# Tube.net
KiCad netlist of a schematic drawn in Altium Designer
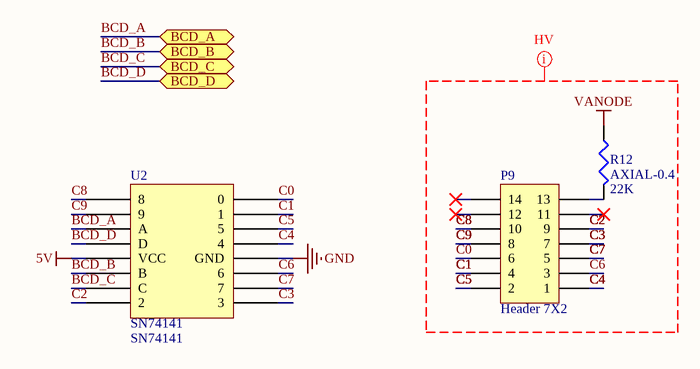
[diagram p0: Tube.SchDoc]

(export (version "E")
  (design (tool "Eeschema 10.0.6"))
  (components
    (comp (ref "P9")
      (value "Header 7X2")
      (footprint "HDR2X7")
      (description "Header, 7-Pin, Dual row")
      (fields (field (name "PUBLISHER") "Altium Limited"))
      (libsource (lib "Miscellaneous Connectors") (part "Header 7X2"))
    )
    (comp (ref "R12")
      (value "AXIAL-0.4")
      (footprint "AXIAL-0.4")
      (description "Resistor")
      (fields (field (name "ALTIUM_VALUE") "22K") (field (name "PUBLISHER") "Altium Limited"))
      (libsource (lib "Miscellaneous Devices") (part "Res3"))
    )
    (comp (ref "U2")
      (value "SN74141")
      (footprint "DIP-16")
      (description "BCD-to-Decimal Driver")
      (fields (field (name "PARTNUMBER") "SN74141"))
      (libsource (lib "Schematic_Components") (part "BCD-to-Decimal Driver"))
    )
  )
  (nets
    (net (code "1") (name "/BCD_A") (class "Default")
      (node (ref "U2") (pin "3") (pinfunction "A_3") (pintype "passive"))
    )
    (net (code "2") (name "/BCD_B") (class "Default")
      (node (ref "U2") (pin "6") (pinfunction "B_6") (pintype "passive"))
    )
    (net (code "3") (name "/BCD_C") (class "Default")
      (node (ref "U2") (pin "7") (pinfunction "C_7") (pintype "passive"))
    )
    (net (code "4") (name "/BCD_D") (class "Default")
      (node (ref "U2") (pin "4") (pinfunction "D_4") (pintype "passive"))
    )
    (net (code "5") (name "/C0") (class "Default")
      (node (ref "P9") (pin "6") (pinfunction "6_6") (pintype "passive"))
      (node (ref "U2") (pin "16") (pinfunction "0_16") (pintype "passive"))
    )
    (net (code "6") (name "/C1") (class "Default")
      (node (ref "P9") (pin "4") (pinfunction "4_4") (pintype "passive"))
      (node (ref "U2") (pin "15") (pinfunction "1_15") (pintype "passive"))
    )
    (net (code "7") (name "/C2") (class "Default")
      (node (ref "P9") (pin "9") (pinfunction "9_9") (pintype "passive"))
      (node (ref "U2") (pin "8") (pinfunction "2_8") (pintype "passive"))
    )
    (net (code "8") (name "/C3") (class "Default")
      (node (ref "P9") (pin "7") (pinfunction "7_7") (pintype "passive"))
      (node (ref "U2") (pin "9") (pinfunction "3_9") (pintype "passive"))
    )
    (net (code "9") (name "/C4") (class "Default")
      (node (ref "P9") (pin "1") (pinfunction "1_1") (pintype "passive"))
      (node (ref "U2") (pin "13") (pinfunction "4_13") (pintype "passive"))
    )
    (net (code "10") (name "/C5") (class "Default")
      (node (ref "P9") (pin "2") (pinfunction "2_2") (pintype "passive"))
      (node (ref "U2") (pin "14") (pinfunction "5_14") (pintype "passive"))
    )
    (net (code "11") (name "/C6") (class "Default")
      (node (ref "P9") (pin "3") (pinfunction "3_3") (pintype "passive"))
      (node (ref "U2") (pin "11") (pinfunction "6_11") (pintype "passive"))
    )
    (net (code "12") (name "/C7") (class "Default")
      (node (ref "P9") (pin "5") (pinfunction "5_5") (pintype "passive"))
      (node (ref "U2") (pin "10") (pinfunction "7_10") (pintype "passive"))
    )
    (net (code "13") (name "/C8") (class "Default")
      (node (ref "P9") (pin "10") (pinfunction "10_10") (pintype "passive"))
      (node (ref "U2") (pin "1") (pinfunction "8_1") (pintype "passive"))
    )
    (net (code "14") (name "/C9") (class "Default")
      (node (ref "P9") (pin "8") (pinfunction "8_8") (pintype "passive"))
      (node (ref "U2") (pin "2") (pinfunction "9_2") (pintype "passive"))
    )
    (net (code "15") (name "5V") (class "Default")
      (node (ref "U2") (pin "5") (pinfunction "VCC_5") (pintype "passive"))
    )
    (net (code "16") (name "GND") (class "Default")
      (node (ref "U2") (pin "12") (pinfunction "GND_12") (pintype "passive"))
    )
    (net (code "17") (name "Net-(P9-Pad13)") (class "Default")
      (node (ref "P9") (pin "13") (pinfunction "13_13") (pintype "passive"))
      (node (ref "R12") (pin "2") (pinfunction "2_2") (pintype "passive"))
    )
    (net (code "18") (name "VANODE") (class "Default")
      (node (ref "R12") (pin "1") (pinfunction "1_1") (pintype "passive"))
    )
    (net (code "19") (name "unconnected-(P9-Pad11)") (class "Default")
      (node (ref "P9") (pin "11") (pinfunction "11_11") (pintype "passive+no_connect"))
    )
    (net (code "20") (name "unconnected-(P9-Pad12)") (class "Default")
      (node (ref "P9") (pin "12") (pinfunction "12_12") (pintype "passive+no_connect"))
    )
    (net (code "21") (name "unconnected-(P9-Pad14)") (class "Default")
      (node (ref "P9") (pin "14") (pinfunction "14_14") (pintype "passive+no_connect"))
    )
  )
)
